# TOP.net
KiCad netlist of a schematic drawn in Altium Designer
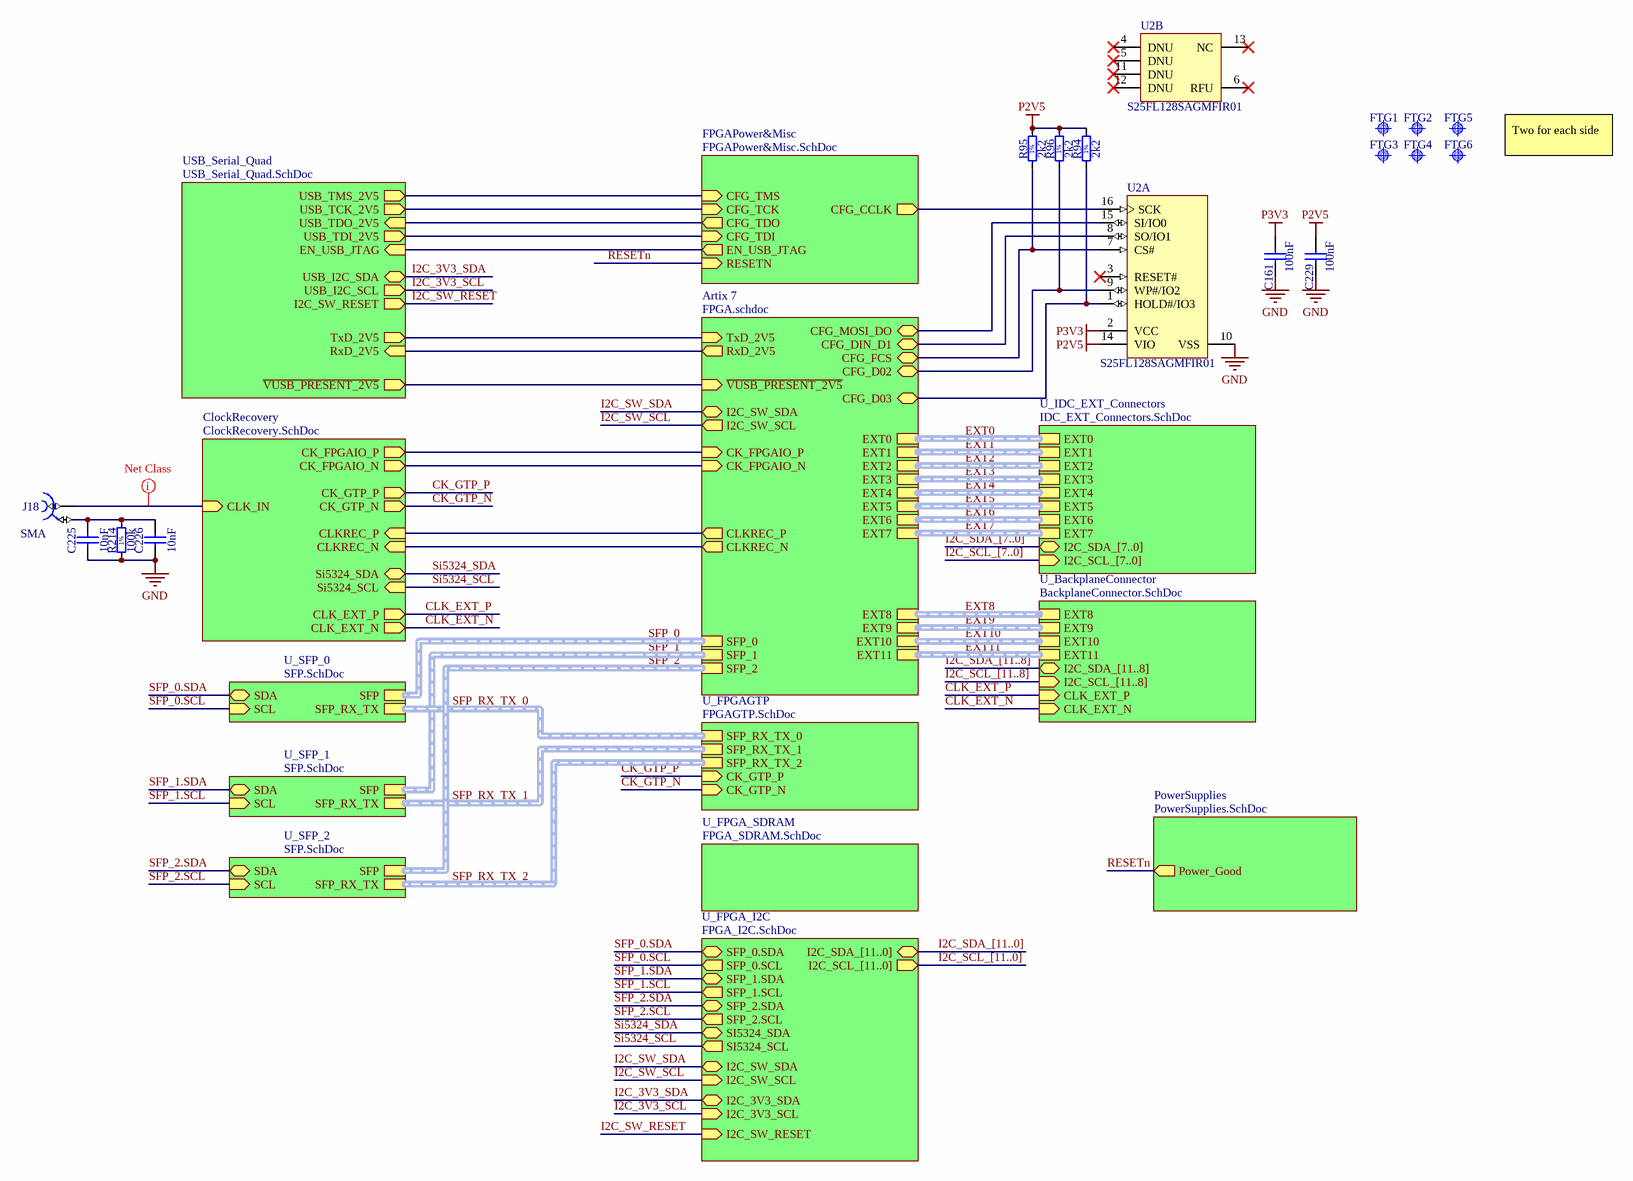
[diagram p0: TOP.SchDoc]

(export (version "E")
  (design (tool "Eeschema 10.0.6"))
  (components
    (comp (ref "C161")
      (value "100nF")
      (footprint "CAPC0603X33N")
      (description "Non-polarised capacitor")
      (fields
        (field (name "PART NUMBER") "CC0201_100NF_6.3V_10%_X5R")
        (field (name "VOLTAGE") "6.3V")
        (field (name "AUTHOR") "CERN DEM JLC")
      )
      (libsource (lib "Capacitors") (part "Capacitor - non polarized"))
    )
    (comp (ref "C225")
      (value "10nF")
      (footprint "CAPC1005X55N")
      (description "Non-polarised capacitor")
      (fields
        (field (name "PART NUMBER") "CC0402_10NF_16V_10%_X7R")
        (field (name "VOLTAGE") "16V")
        (field (name "AUTHOR") "CERN DEM JLC")
      )
      (libsource (lib "Capacitors") (part "Capacitor - non polarized"))
    )
    (comp (ref "C226")
      (value "10nF")
      (footprint "CAPC1005X55N")
      (description "Non-polarised capacitor")
      (fields
        (field (name "PART NUMBER") "CC0402_10NF_16V_10%_X7R")
        (field (name "VOLTAGE") "16V")
        (field (name "AUTHOR") "CERN DEM JLC")
      )
      (libsource (lib "Capacitors") (part "Capacitor - non polarized"))
    )
    (comp (ref "C229")
      (value "100nF")
      (footprint "CAPC0603X33N")
      (description "Non-polarised capacitor")
      (fields
        (field (name "PART NUMBER") "CC0201_100NF_6.3V_10%_X5R")
        (field (name "VOLTAGE") "6.3V")
        (field (name "AUTHOR") "CERN DEM JLC")
      )
      (libsource (lib "Capacitors") (part "Capacitor - non polarized"))
    )
    (comp (ref "FTG1")
      (value "Use only in PCB")
      (footprint "FIDUCIAL_TOP_C100-200")
      (description "Fiducial Target")
      (fields (field (name "PART NUMBER") "FIDUCIAL_TARGET_C100-200") (field (name "AUTHOR") "CERN DEM JLC"))
      (libsource (lib "Eletro-mechanical") (part "Fiducial Target"))
    )
    (comp (ref "FTG2")
      (value "Use only in PCB")
      (footprint "FIDUCIAL_TOP_S100-200")
      (description "Fiducial Target")
      (fields (field (name "PART NUMBER") "FIDUCIAL_TARGET_S100-200") (field (name "AUTHOR") "CERN DEM JLC"))
      (libsource (lib "Eletro-mechanical") (part "Fiducial Target"))
    )
    (comp (ref "FTG3")
      (value "Use only in PCB")
      (footprint "FIDUCIAL_TOP_C100-200")
      (description "Fiducial Target")
      (fields (field (name "PART NUMBER") "FIDUCIAL_TARGET_C100-200") (field (name "AUTHOR") "CERN DEM JLC"))
      (libsource (lib "Eletro-mechanical") (part "Fiducial Target"))
    )
    (comp (ref "FTG4")
      (value "Use only in PCB")
      (footprint "FIDUCIAL_TOP_C100-200")
      (description "Fiducial Target")
      (fields (field (name "PART NUMBER") "FIDUCIAL_TARGET_C100-200") (field (name "AUTHOR") "CERN DEM JLC"))
      (libsource (lib "Eletro-mechanical") (part "Fiducial Target"))
    )
    (comp (ref "FTG5")
      (value "Use only in PCB")
      (footprint "FIDUCIAL_TOP_C100-200")
      (description "Fiducial Target")
      (fields (field (name "PART NUMBER") "FIDUCIAL_TARGET_C100-200") (field (name "AUTHOR") "CERN DEM JLC"))
      (libsource (lib "Eletro-mechanical") (part "Fiducial Target"))
    )
    (comp (ref "FTG6")
      (value "Use only in PCB")
      (footprint "FIDUCIAL_TOP_S100-200")
      (description "Fiducial Target")
      (fields (field (name "PART NUMBER") "FIDUCIAL_TARGET_S100-200") (field (name "AUTHOR") "CERN DEM JLC"))
      (libsource (lib "Eletro-mechanical") (part "Fiducial Target"))
    )
    (comp (ref "J18")
      (value "SMA")
      (footprint "AMPHENOL_132203")
      (fields
        (field (name "PART NUMBER") "AMPHENOL_132203")
        (field (name "MANUFACTURER") "AMPHENOL")
        (field (name "MANUFACTURER PART NUMBER") "132203")
        (field (name "AUTHOR") "CERN DEM MR")
      )
      (libsource (lib "Connectors") (part "Coax_1Female_1Shield"))
    )
    (comp (ref "R94")
      (value "2k2")
      (footprint "RESC1005X40N")
      (description "Resistor - 1%")
      (fields
        (field (name "PART NUMBER") "R0402_2K2_1%_0.0625W_100PPM")
        (field (name "POWER") "0.0625W")
        (field (name "AUTHOR") "CERN DEM JLC")
      )
      (libsource (lib "Resistors") (part "Resistor - 1%"))
    )
    (comp (ref "R95")
      (value "2k2")
      (footprint "RESC1005X40N")
      (description "Resistor - 1%")
      (fields
        (field (name "PART NUMBER") "R0402_2K2_1%_0.0625W_100PPM")
        (field (name "POWER") "0.0625W")
        (field (name "AUTHOR") "CERN DEM JLC")
      )
      (libsource (lib "Resistors") (part "Resistor - 1%"))
    )
    (comp (ref "R96")
      (value "2k2")
      (footprint "RESC1005X40N")
      (description "Resistor - 1%")
      (fields
        (field (name "PART NUMBER") "R0402_2K2_1%_0.0625W_100PPM")
        (field (name "POWER") "0.0625W")
        (field (name "AUTHOR") "CERN DEM JLC")
      )
      (libsource (lib "Resistors") (part "Resistor - 1%"))
    )
    (comp (ref "R214")
      (value "100k")
      (footprint "RESC1005X40N")
      (description "Resistor - 1%")
      (fields
        (field (name "PART NUMBER") "R0402_100K_1%_0.0625W_100PPM")
        (field (name "MANUFACTURER") "GENERIC")
        (field (name "AUTHOR") "CERN DEM JLC")
      )
      (libsource (lib "Resistors") (part "Resistor - 1%"))
    )
    (comp (ref "U2")
      (value "S25FL128SAGMFIR01")
      (footprint "SPSN-SOIC-16_N")
      (fields (field (name "MANUFACTURER") "Spansion"))
      (libsource (lib "Altium Content Vault") (part "SPSN-S25FL128S-16_A"))
    )
  )
  (nets
    (net (code "43") (name "/CFG_CCLK") (class "Default")
      (node (ref "U2") (pin "16") (pinfunction "SCK_16") (pintype "input"))
    )
    (net (code "44") (name "/CFG_D02") (class "Default")
      (node (ref "R96") (pin "1") (pinfunction "1_1") (pintype "passive"))
      (node (ref "U2") (pin "9") (pinfunction "WP#/IO2_9") (pintype "bidirectional"))
    )
    (net (code "45") (name "/CFG_D03") (class "Default")
      (node (ref "R94") (pin "1") (pinfunction "1_1") (pintype "passive"))
      (node (ref "U2") (pin "1") (pinfunction "HOLD#/IO3_1") (pintype "bidirectional"))
    )
    (net (code "46") (name "/CFG_DIN_D1") (class "Default")
      (node (ref "U2") (pin "8") (pinfunction "SO/IO1_8") (pintype "bidirectional"))
    )
    (net (code "47") (name "/CFG_FCS") (class "Default")
      (node (ref "R95") (pin "1") (pinfunction "1_1") (pintype "passive"))
      (node (ref "U2") (pin "7") (pinfunction "CS#_7") (pintype "input"))
    )
    (net (code "48") (name "/CFG_MOSI_DO") (class "Default")
      (node (ref "U2") (pin "15") (pinfunction "SI/IO0_15") (pintype "bidirectional"))
    )
    (net (code "58") (name "/CLK_IN") (class "Default")
      (node (ref "J18") (pin "1") (pinfunction "1_1") (pintype "bidirectional"))
    )
    (net (code "104") (name "GND") (class "Default")
      (node (ref "C161") (pin "1") (pinfunction "1_1") (pintype "passive"))
      (node (ref "C225") (pin "1") (pinfunction "1_1") (pintype "passive"))
      (node (ref "C226") (pin "1") (pinfunction "1_1") (pintype "passive"))
      (node (ref "C229") (pin "1") (pinfunction "1_1") (pintype "passive"))
      (node (ref "R214") (pin "1") (pinfunction "1_1") (pintype "passive"))
      (node (ref "U2") (pin "10") (pinfunction "VSS_10") (pintype "power_in"))
    )
    (net (code "105") (name "Net-(C225-Pad2)") (class "Default")
      (node (ref "C225") (pin "2") (pinfunction "2_2") (pintype "passive"))
      (node (ref "C226") (pin "2") (pinfunction "2_2") (pintype "passive"))
      (node (ref "J18") (pin "2") (pinfunction "2_2") (pintype "bidirectional"))
      (node (ref "R214") (pin "2") (pinfunction "2_2") (pintype "passive"))
    )
    (net (code "106") (name "P2V5") (class "Default")
      (node (ref "C229") (pin "2") (pinfunction "2_2") (pintype "passive"))
      (node (ref "R94") (pin "2") (pinfunction "2_2") (pintype "passive"))
      (node (ref "R95") (pin "2") (pinfunction "2_2") (pintype "passive"))
      (node (ref "R96") (pin "2") (pinfunction "2_2") (pintype "passive"))
      (node (ref "U2") (pin "14") (pinfunction "VIO_14") (pintype "power_in"))
    )
    (net (code "107") (name "P3V3") (class "Default")
      (node (ref "C161") (pin "2") (pinfunction "2_2") (pintype "passive"))
      (node (ref "U2") (pin "2") (pinfunction "VCC_2") (pintype "power_in"))
    )
    (net (code "108") (name "unconnected-(U2A-RESET#-Pad3)") (class "Default")
      (node (ref "U2") (pin "3") (pinfunction "RESET#_3") (pintype "input+no_connect"))
    )
    (net (code "109") (name "unconnected-(U2B-DNU-Pad4)") (class "Default")
      (node (ref "U2") (pin "4") (pinfunction "DNU_4") (pintype "passive+no_connect"))
    )
    (net (code "110") (name "unconnected-(U2B-DNU-Pad5)") (class "Default")
      (node (ref "U2") (pin "5") (pinfunction "DNU_5") (pintype "passive+no_connect"))
    )
    (net (code "111") (name "unconnected-(U2B-DNU-Pad11)") (class "Default")
      (node (ref "U2") (pin "11") (pinfunction "DNU_11") (pintype "passive+no_connect"))
    )
    (net (code "112") (name "unconnected-(U2B-DNU-Pad12)") (class "Default")
      (node (ref "U2") (pin "12") (pinfunction "DNU_12") (pintype "passive+no_connect"))
    )
    (net (code "113") (name "unconnected-(U2B-NC-Pad13)") (class "Default")
      (node (ref "U2") (pin "13") (pinfunction "NC_13") (pintype "passive+no_connect"))
    )
    (net (code "114") (name "unconnected-(U2B-RFU-Pad6)") (class "Default")
      (node (ref "U2") (pin "6") (pinfunction "RFU_6") (pintype "passive+no_connect"))
    )
  )
)
